# Landing_Gear_Layout_REV.net
KiCad netlist of a schematic drawn in EAGLE
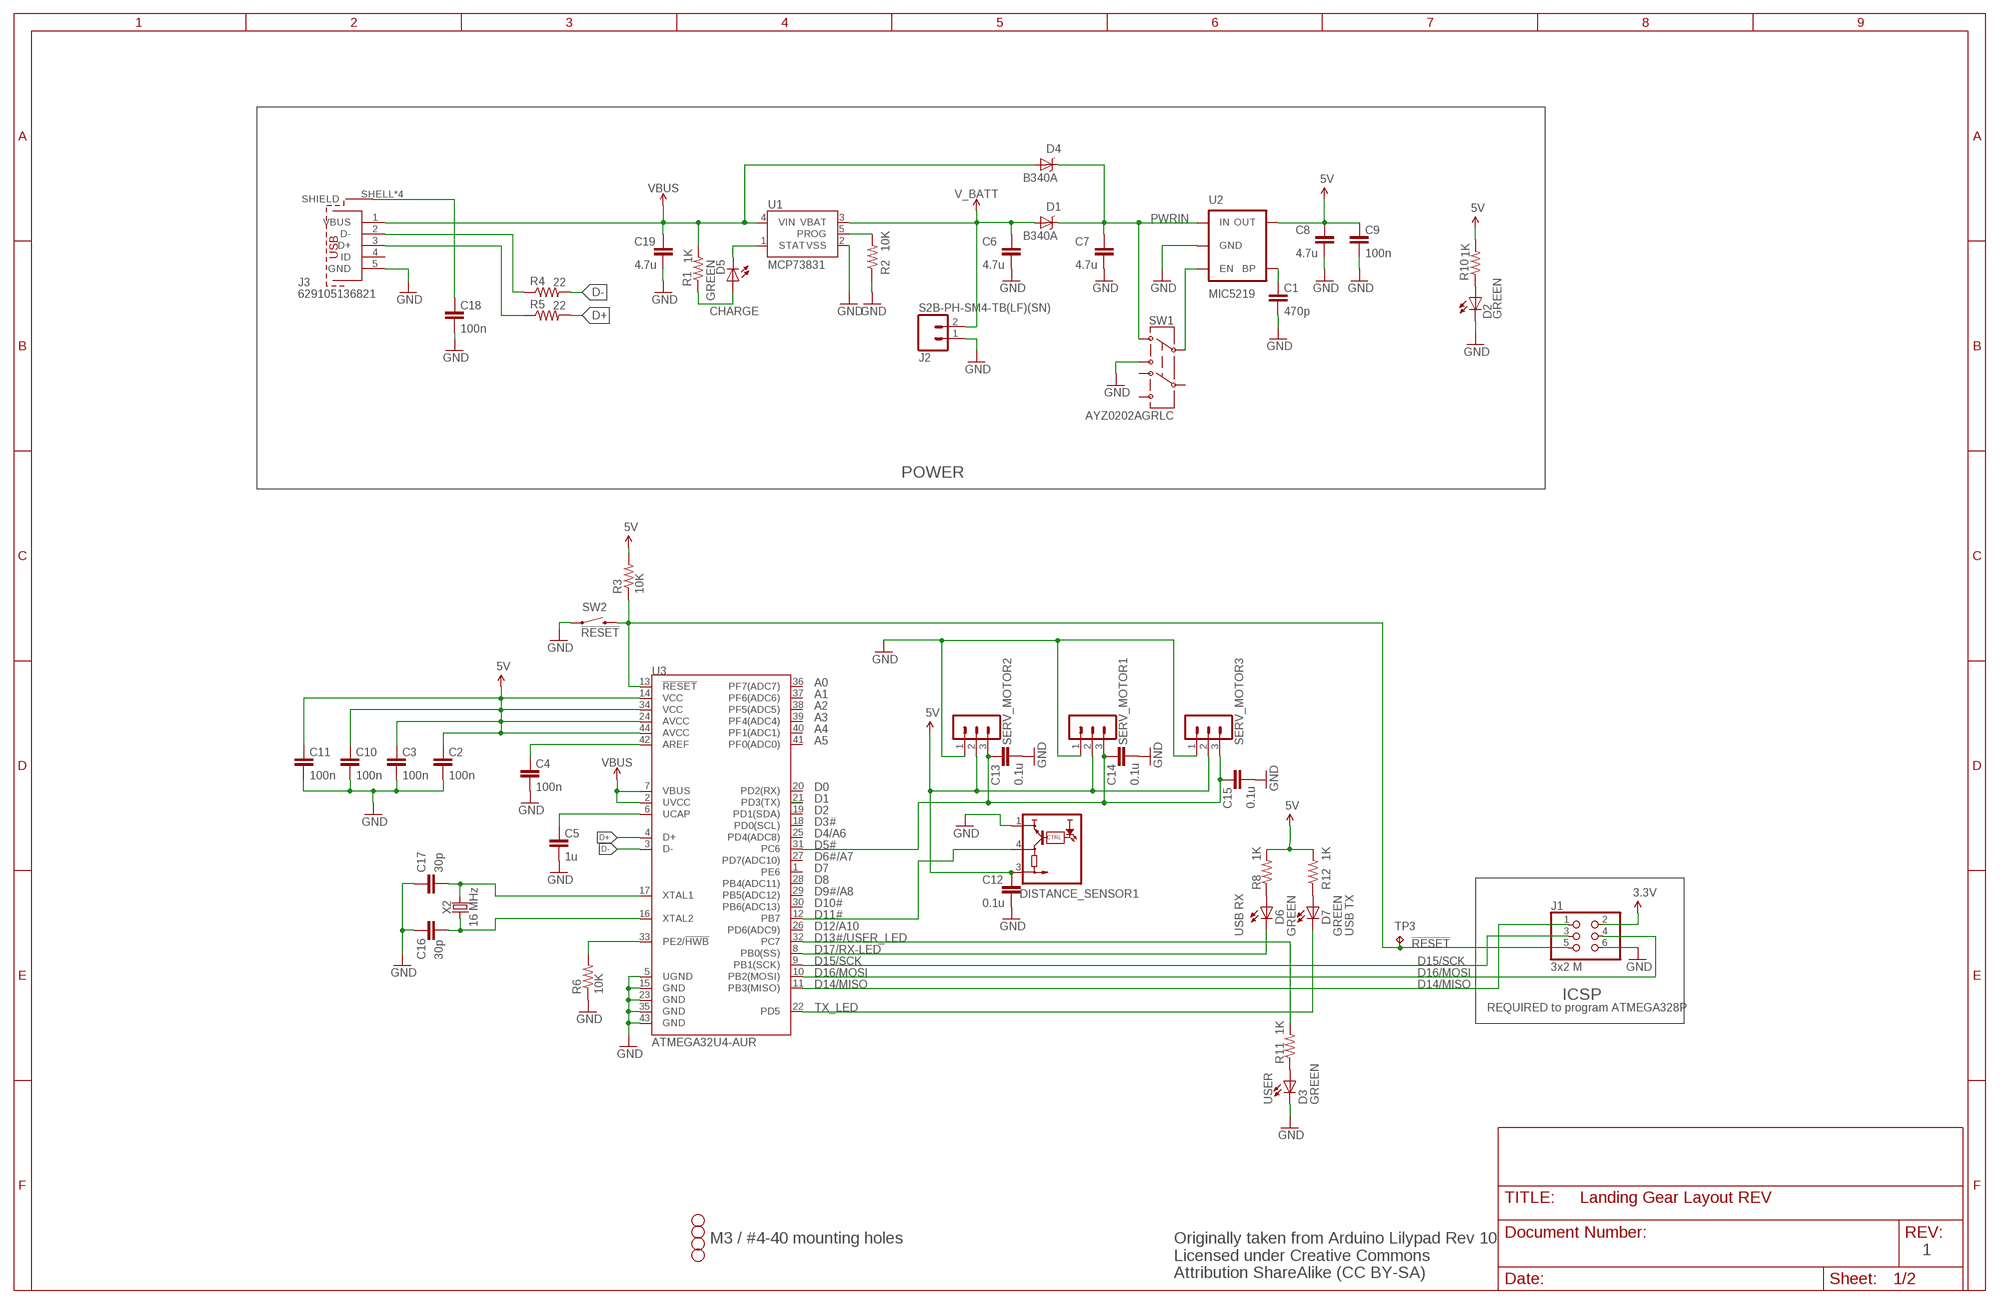
[diagram p0: schematic, sheet 1]

(export (version "E")
  (design (tool "Eeschema 10.0.6"))
  (components
    (comp (ref "C1")
      (value "470p")
      (footprint "eagle-import:C0805K")
      (fields (field (name "MFR") "Samsung") (field (name "MPN") "CL21B471KBANNNC"))
      (libsource (lib "eagle-import") (part "C-EUC0805K"))
    )
    (comp (ref "C2")
      (value "100n")
      (footprint "eagle-import:C0805K")
      (fields (field (name "MFR") "Samsung") (field (name "MPN") "CL21B104KBCNNNC"))
      (libsource (lib "eagle-import") (part "C-EUC0805K"))
    )
    (comp (ref "C3")
      (value "100n")
      (footprint "eagle-import:C0805K")
      (fields (field (name "MFR") "Samsung") (field (name "MPN") "CL21B104KBCNNNC"))
      (libsource (lib "eagle-import") (part "C-EUC0805K"))
    )
    (comp (ref "C4")
      (value "100n")
      (footprint "eagle-import:C0805K")
      (fields (field (name "MFR") "Samsung") (field (name "MPN") "CL21B104KBCNNNC"))
      (libsource (lib "eagle-import") (part "C-EUC0805K"))
    )
    (comp (ref "C5")
      (value "1u")
      (footprint "eagle-import:C0805K")
      (fields (field (name "MFR") "Samsung") (field (name "MPN") "CL21B105KOFNNNG"))
      (libsource (lib "eagle-import") (part "C-EUC0805K"))
    )
    (comp (ref "C6")
      (value "4.7u")
      (footprint "eagle-import:C0805K")
      (fields (field (name "MFR") "Samsung") (field (name "MPN") "CL21A475KOFNNNE"))
      (libsource (lib "eagle-import") (part "C-EUC0805K"))
    )
    (comp (ref "C7")
      (value "4.7u")
      (footprint "eagle-import:C0805K")
      (fields (field (name "MFR") "Samsung") (field (name "MPN") "CL21A475KOFNNNE"))
      (libsource (lib "eagle-import") (part "C-EUC0805K"))
    )
    (comp (ref "C8")
      (value "4.7u")
      (footprint "eagle-import:C0805K")
      (fields (field (name "MFR") "Samsung") (field (name "MPN") "CL21A475KOFNNNE"))
      (libsource (lib "eagle-import") (part "C-EUC0805K"))
    )
    (comp (ref "C9")
      (value "100n")
      (footprint "eagle-import:C0805K")
      (fields (field (name "MFR") "Samsung") (field (name "MPN") "CL21B104KBCNNNC"))
      (libsource (lib "eagle-import") (part "C-EUC0805K"))
    )
    (comp (ref "C10")
      (value "100n")
      (footprint "eagle-import:C0805K")
      (fields (field (name "MFR") "Samsung") (field (name "MPN") "CL21B104KBCNNNC"))
      (libsource (lib "eagle-import") (part "C-EUC0805K"))
    )
    (comp (ref "C11")
      (value "100n")
      (footprint "eagle-import:C0805K")
      (fields (field (name "MFR") "Samsung") (field (name "MPN") "CL21B104KBCNNNC"))
      (libsource (lib "eagle-import") (part "C-EUC0805K"))
    )
    (comp (ref "C12")
      (value "0.1u")
      (footprint "eagle-import:C0805K")
      (fields (field (name "MFR") "Samsung") (field (name "MPN") "CL21B105KOFNNNG"))
      (libsource (lib "eagle-import") (part "C-EUC0805K"))
    )
    (comp (ref "C13")
      (value "0.1u")
      (footprint "eagle-import:C0805K")
      (fields (field (name "MFR") "Samsung") (field (name "MPN") "CL21B105KOFNNNG"))
      (libsource (lib "eagle-import") (part "C-EUC0805K"))
    )
    (comp (ref "C14")
      (value "0.1u")
      (footprint "eagle-import:C0805K")
      (fields (field (name "MFR") "Samsung") (field (name "MPN") "CL21B105KOFNNNG"))
      (libsource (lib "eagle-import") (part "C-EUC0805K"))
    )
    (comp (ref "C15")
      (value "0.1u")
      (footprint "eagle-import:C0805K")
      (fields (field (name "MFR") "Samsung") (field (name "MPN") "CL21B105KOFNNNG"))
      (libsource (lib "eagle-import") (part "C-EUC0805K"))
    )
    (comp (ref "C16")
      (value "30p")
      (footprint "eagle-import:C0805K")
      (fields (field (name "MFR") "Samsung") (field (name "MPN") "CL21C300JBANNNC"))
      (libsource (lib "eagle-import") (part "C-EUC0805K"))
    )
    (comp (ref "C17")
      (value "30p")
      (footprint "eagle-import:C0805K")
      (fields (field (name "MFR") "Samsung") (field (name "MPN") "CL21C180JBANNNC"))
      (libsource (lib "eagle-import") (part "C-EUC0805K"))
    )
    (comp (ref "C18")
      (value "100n")
      (footprint "eagle-import:C0805K")
      (fields (field (name "MFR") "Samsung") (field (name "MPN") "CL21B104KBCNNNC"))
      (libsource (lib "eagle-import") (part "C-EUC0805K"))
    )
    (comp (ref "C19")
      (value "4.7u")
      (footprint "eagle-import:C0805K")
      (fields (field (name "MFR") "Samsung") (field (name "MPN") "CL21A475KOFNNNE"))
      (libsource (lib "eagle-import") (part "C-EUC0805K"))
    )
    (comp (ref "D1")
      (value "B340A")
      (footprint "eagle-import:SMA-DIODE")
      (fields (field (name "MFR") "Diodes Inc") (field (name "MPN") "B340AE-13"))
      (libsource (lib "eagle-import") (part "DIODE-SCHOTTKY_"))
    )
    (comp (ref "D2")
      (value "GREEN")
      (footprint "eagle-import:CHIP-LED0805")
      (fields (field (name "MFR") "Würth Elektronik") (field (name "MPN") "150080GS75000"))
      (libsource (lib "eagle-import") (part "LEDCHIP-LED0805"))
    )
    (comp (ref "D3")
      (value "GREEN")
      (footprint "eagle-import:CHIP-LED0805")
      (fields (field (name "MFR") "Würth Elektronik") (field (name "MPN") "150080GS75000"))
      (libsource (lib "eagle-import") (part "LEDCHIP-LED0805"))
    )
    (comp (ref "D4")
      (value "B340A")
      (footprint "eagle-import:SMA-DIODE")
      (fields (field (name "MFR") "Diodes Inc") (field (name "MPN") "B340AE-13"))
      (libsource (lib "eagle-import") (part "DIODE-SCHOTTKY_"))
    )
    (comp (ref "D5")
      (value "GREEN")
      (footprint "eagle-import:CHIP-LED0805")
      (fields (field (name "MFR") "Würth Elektronik") (field (name "MPN") "150080GS75000"))
      (libsource (lib "eagle-import") (part "LEDCHIP-LED0805"))
    )
    (comp (ref "D6")
      (value "GREEN")
      (footprint "eagle-import:CHIP-LED0805")
      (fields (field (name "MFR") "Würth Elektronik") (field (name "MPN") "150080GS75000"))
      (libsource (lib "eagle-import") (part "LEDCHIP-LED0805"))
    )
    (comp (ref "D7")
      (value "GREEN")
      (footprint "eagle-import:CHIP-LED0805")
      (fields (field (name "MFR") "Würth Elektronik") (field (name "MPN") "150080GS75000"))
      (libsource (lib "eagle-import") (part "LEDCHIP-LED0805"))
    )
    (comp (ref "DISTANCE_SENSOR1")
      (value "TSSP6P38")
      (footprint "eagle-import:TSSP6P38")
      (libsource (lib "eagle-import") (part "TSSP6P38"))
    )
    (comp (ref "H1")
      (value "STAND-OFF")
      (footprint "eagle-import:STAND-OFF")
      (libsource (lib "eagle-import") (part "STAND-OFF"))
    )
    (comp (ref "H2")
      (value "STAND-OFF")
      (footprint "eagle-import:STAND-OFF")
      (libsource (lib "eagle-import") (part "STAND-OFF"))
    )
    (comp (ref "H3")
      (value "STAND-OFF")
      (footprint "eagle-import:STAND-OFF")
      (libsource (lib "eagle-import") (part "STAND-OFF"))
    )
    (comp (ref "H4")
      (value "STAND-OFF")
      (footprint "eagle-import:STAND-OFF")
      (libsource (lib "eagle-import") (part "STAND-OFF"))
    )
    (comp (ref "J1")
      (value "3x2 M")
      (footprint "eagle-import:2X03")
      (fields (field (name "MFR") "Harwin") (field (name "MPN") "M20-9980345"))
      (libsource (lib "eagle-import") (part "PINHD-2X3"))
    )
    (comp (ref "J2")
      (value "S2B-PH-SM4-TB(LF)(SN)")
      (footprint "eagle-import:JST-2-SMD")
      (fields (field (name "MFR") "JST"))
      (libsource (lib "eagle-import") (part "M02-JST-2MM-SMT"))
    )
    (comp (ref "J3")
      (value "629105136821")
      (footprint "eagle-import:629105136821")
      (fields (field (name "MFR") "Wurth"))
      (libsource (lib "eagle-import") (part "629105136821"))
    )
    (comp (ref "R1")
      (value "1K")
      (footprint "eagle-import:R0805")
      (fields (field (name "MFR") "Yageo") (field (name "MPN") "RC0805FR-071KL"))
      (libsource (lib "eagle-import") (part "R-US_R0805"))
    )
    (comp (ref "R2")
      (value "10K")
      (footprint "eagle-import:R0805")
      (fields (field (name "MFR") "Yageo") (field (name "MPN") "RC0805FR-0710KL"))
      (libsource (lib "eagle-import") (part "R-US_R0805"))
    )
    (comp (ref "R3")
      (value "10K")
      (footprint "eagle-import:R0805")
      (fields (field (name "MFR") "Yageo") (field (name "MPN") "RC0805FR-0710KL"))
      (libsource (lib "eagle-import") (part "R-US_R0805"))
    )
    (comp (ref "R4")
      (value "22")
      (footprint "eagle-import:R0805")
      (fields (field (name "MFR") "Yageo") (field (name "MPN") "RC0805FR-0722RL"))
      (libsource (lib "eagle-import") (part "R-US_R0805"))
    )
    (comp (ref "R5")
      (value "22")
      (footprint "eagle-import:R0805")
      (fields (field (name "MFR") "Yageo") (field (name "MPN") "RC0805FR-0722RL"))
      (libsource (lib "eagle-import") (part "R-US_R0805"))
    )
    (comp (ref "R6")
      (value "10K")
      (footprint "eagle-import:R0805")
      (fields (field (name "MFR") "Yageo") (field (name "MPN") "RC0805FR-0710KL"))
      (libsource (lib "eagle-import") (part "R-US_R0805"))
    )
    (comp (ref "R8")
      (value "1K")
      (footprint "eagle-import:R0805")
      (fields (field (name "MFR") "Yageo") (field (name "MPN") "RC0805FR-071KL"))
      (libsource (lib "eagle-import") (part "R-US_R0805"))
    )
    (comp (ref "R10")
      (value "1K")
      (footprint "eagle-import:R0805")
      (fields (field (name "MFR") "Yageo") (field (name "MPN") "RC0805FR-071KL"))
      (libsource (lib "eagle-import") (part "R-US_R0805"))
    )
    (comp (ref "R11")
      (value "1K")
      (footprint "eagle-import:R0805")
      (fields (field (name "MFR") "Yageo") (field (name "MPN") "RC0805FR-071KL"))
      (libsource (lib "eagle-import") (part "R-US_R0805"))
    )
    (comp (ref "R12")
      (value "1K")
      (footprint "eagle-import:R0805")
      (fields (field (name "MFR") "Yageo") (field (name "MPN") "RC0805FR-071KL"))
      (libsource (lib "eagle-import") (part "R-US_R0805"))
    )
    (comp (ref "SERV_MOTOR1")
      (value "MA03-1")
      (footprint "eagle-import:MA03-1")
      (libsource (lib "eagle-import") (part "MA03-1"))
    )
    (comp (ref "SERV_MOTOR2")
      (value "MA03-1")
      (footprint "eagle-import:MA03-1")
      (libsource (lib "eagle-import") (part "MA03-1"))
    )
    (comp (ref "SERV_MOTOR3")
      (value "MA03-1")
      (footprint "eagle-import:MA03-1")
      (libsource (lib "eagle-import") (part "MA03-1"))
    )
    (comp (ref "SW1")
      (value "AYZ0202AGRLC")
      (footprint "eagle-import:AYZ0202")
      (fields (field (name "MFR") "C&K"))
      (libsource (lib "eagle-import") (part "SWITCH-DPDTSMD"))
    )
    (comp (ref "SW2")
      (value "!RESET")
      (footprint "eagle-import:TACTILE_SWITCH_SMD")
      (fields (field (name "MFR") "C&K") (field (name "MPN") "RS-187R05A2-DS MT RT"))
      (libsource (lib "eagle-import") (part "SWITCH-MOMENTARY-2SMD"))
    )
    (comp (ref "TP3")
      (value "TPPAD1-13")
      (footprint "eagle-import:P1-13")
      (libsource (lib "eagle-import") (part "TPPAD1-13"))
    )
    (comp (ref "U1")
      (value "MCP73831")
      (footprint "eagle-import:SOT23-5")
      (fields (field (name "MFR") "Microchip") (field (name "MPN") "MCP73831T-2ACI/OT"))
      (libsource (lib "eagle-import") (part "MCP73831"))
    )
    (comp (ref "U2")
      (value "MIC5219")
      (footprint "eagle-import:SOT23-5")
      (fields (field (name "MFR") "Microchip") (field (name "MPN") "MIC5219-3.3YM5-TR"))
      (libsource (lib "eagle-import") (part "V_REG_MIC5219SMD"))
    )
    (comp (ref "U3")
      (value "ATMEGA32U4-AUR")
      (footprint "eagle-import:TQFP44")
      (fields (field (name "MFR") "Microchip") (field (name "PROD_ID") "IC-10828"))
      (libsource (lib "eagle-import") (part "ATMEGA32U4TQFP-44"))
    )
    (comp (ref "X2")
      (value "16 MHz")
      (footprint "eagle-import:HC49UP")
      (fields (field (name "MFR") "ECS") (field (name "MPN") "ECS-160-18-5PX-TR"))
      (libsource (lib "eagle-import") (part "CRYSTALSMD-HC49UP"))
    )
  )
  (nets
    (net (code "1") (name "3.3V") (class "Default")
      (node (ref "C10") (pin "1") (pinfunction "1_1") (pintype "passive"))
      (node (ref "C11") (pin "1") (pinfunction "1_1") (pintype "passive"))
      (node (ref "C12") (pin "1") (pinfunction "1_1") (pintype "passive"))
      (node (ref "C2") (pin "1") (pinfunction "1_1") (pintype "passive"))
      (node (ref "C3") (pin "1") (pinfunction "1_1") (pintype "passive"))
      (node (ref "C8") (pin "1") (pinfunction "1_1") (pintype "passive"))
      (node (ref "C9") (pin "1") (pinfunction "1_1") (pintype "passive"))
      (node (ref "DISTANCE_SENSOR1") (pin "3") (pinfunction "VS_3") (pintype "power_in"))
      (node (ref "J1") (pin "2") (pinfunction "2_2") (pintype "passive"))
      (node (ref "R10") (pin "2") (pinfunction "2_2") (pintype "passive"))
      (node (ref "R12") (pin "2") (pinfunction "2_2") (pintype "passive"))
      (node (ref "R3") (pin "2") (pinfunction "2_2") (pintype "passive"))
      (node (ref "R8") (pin "2") (pinfunction "2_2") (pintype "passive"))
      (node (ref "SERV_MOTOR1") (pin "2") (pinfunction "2_2") (pintype "passive"))
      (node (ref "SERV_MOTOR2") (pin "2") (pinfunction "2_2") (pintype "passive"))
      (node (ref "SERV_MOTOR3") (pin "2") (pinfunction "2_2") (pintype "passive"))
      (node (ref "U2") (pin "5") (pinfunction "OUT_5") (pintype "passive"))
      (node (ref "U3") (pin "14") (pinfunction "VCC_14") (pintype "bidirectional"))
      (node (ref "U3") (pin "24") (pinfunction "AVCC_24") (pintype "bidirectional"))
      (node (ref "U3") (pin "34") (pinfunction "VCC_34") (pintype "bidirectional"))
      (node (ref "U3") (pin "44") (pinfunction "AVCC_44") (pintype "bidirectional"))
    )
    (net (code "2") (name "D+") (class "Default")
      (node (ref "R5") (pin "2") (pinfunction "2_2") (pintype "passive"))
      (node (ref "U3") (pin "4") (pinfunction "D+_4") (pintype "bidirectional"))
    )
    (net (code "3") (name "D-") (class "Default")
      (node (ref "R4") (pin "2") (pinfunction "2_2") (pintype "passive"))
      (node (ref "U3") (pin "3") (pinfunction "D-_3") (pintype "bidirectional"))
    )
    (net (code "4") (name "D13#{slash}USER_LED") (class "Default")
      (node (ref "R11") (pin "2") (pinfunction "2_2") (pintype "passive"))
      (node (ref "U3") (pin "32") (pinfunction "PC7_32") (pintype "bidirectional"))
    )
    (net (code "5") (name "D14{slash}MISO") (class "Default")
      (node (ref "J1") (pin "1") (pinfunction "1_1") (pintype "passive"))
      (node (ref "U3") (pin "11") (pinfunction "PB3(MISO)_11") (pintype "bidirectional"))
    )
    (net (code "6") (name "D15{slash}SCK") (class "Default")
      (node (ref "J1") (pin "3") (pinfunction "3_3") (pintype "passive"))
      (node (ref "U3") (pin "9") (pinfunction "PB1(SCK)_9") (pintype "bidirectional"))
    )
    (net (code "7") (name "D16{slash}MOSI") (class "Default")
      (node (ref "J1") (pin "4") (pinfunction "4_4") (pintype "passive"))
      (node (ref "U3") (pin "10") (pinfunction "PB2(MOSI)_10") (pintype "bidirectional"))
    )
    (net (code "8") (name "D17{slash}RX-LED") (class "Default")
      (node (ref "D6") (pin "C") (pinfunction "C_C") (pintype "passive"))
      (node (ref "U3") (pin "8") (pinfunction "PB0(SS)_8") (pintype "bidirectional"))
    )
    (net (code "9") (name "GND") (class "Default")
      (node (ref "C1") (pin "2") (pinfunction "2_2") (pintype "passive"))
      (node (ref "C10") (pin "2") (pinfunction "2_2") (pintype "passive"))
      (node (ref "C11") (pin "2") (pinfunction "2_2") (pintype "passive"))
      (node (ref "C12") (pin "2") (pinfunction "2_2") (pintype "passive"))
      (node (ref "C13") (pin "2") (pinfunction "2_2") (pintype "passive"))
      (node (ref "C14") (pin "2") (pinfunction "2_2") (pintype "passive"))
      (node (ref "C15") (pin "2") (pinfunction "2_2") (pintype "passive"))
      (node (ref "C16") (pin "2") (pinfunction "2_2") (pintype "passive"))
      (node (ref "C17") (pin "2") (pinfunction "2_2") (pintype "passive"))
      (node (ref "C18") (pin "2") (pinfunction "2_2") (pintype "passive"))
      (node (ref "C19") (pin "2") (pinfunction "2_2") (pintype "passive"))
      (node (ref "C2") (pin "2") (pinfunction "2_2") (pintype "passive"))
      (node (ref "C3") (pin "2") (pinfunction "2_2") (pintype "passive"))
      (node (ref "C4") (pin "2") (pinfunction "2_2") (pintype "passive"))
      (node (ref "C5") (pin "2") (pinfunction "2_2") (pintype "passive"))
      (node (ref "C6") (pin "2") (pinfunction "2_2") (pintype "passive"))
      (node (ref "C7") (pin "2") (pinfunction "2_2") (pintype "passive"))
      (node (ref "C8") (pin "2") (pinfunction "2_2") (pintype "passive"))
      (node (ref "C9") (pin "2") (pinfunction "2_2") (pintype "passive"))
      (node (ref "D2") (pin "C") (pinfunction "C_C") (pintype "passive"))
      (node (ref "D3") (pin "C") (pinfunction "C_C") (pintype "passive"))
      (node (ref "DISTANCE_SENSOR1") (pin "1") (pinfunction "GND_1") (pintype "power_in"))
      (node (ref "J1") (pin "6") (pinfunction "6_6") (pintype "passive"))
      (node (ref "J2") (pin "1") (pinfunction "2_1") (pintype "passive"))
      (node (ref "J3") (pin "5") (pinfunction "GND_5") (pintype "passive"))
      (node (ref "R2") (pin "1") (pinfunction "1_1") (pintype "passive"))
      (node (ref "R6") (pin "1") (pinfunction "1_1") (pintype "passive"))
      (node (ref "SERV_MOTOR1") (pin "1") (pinfunction "1_1") (pintype "passive"))
      (node (ref "SERV_MOTOR2") (pin "1") (pinfunction "1_1") (pintype "passive"))
      (node (ref "SERV_MOTOR3") (pin "1") (pinfunction "1_1") (pintype "passive"))
      (node (ref "SW1") (pin "3") (pinfunction "3_3") (pintype "bidirectional"))
      (node (ref "SW2") (pin "1") (pinfunction "1_1") (pintype "passive"))
      (node (ref "U1") (pin "2") (pinfunction "VSS_2") (pintype "power_in"))
      (node (ref "U2") (pin "2") (pinfunction "GND_2") (pintype "input"))
      (node (ref "U3") (pin "15") (pinfunction "GND_15") (pintype "bidirectional"))
      (node (ref "U3") (pin "23") (pinfunction "GND_23") (pintype "bidirectional"))
      (node (ref "U3") (pin "35") (pinfunction "GND_35") (pintype "bidirectional"))
      (node (ref "U3") (pin "43") (pinfunction "GND_43") (pintype "bidirectional"))
      (node (ref "U3") (pin "5") (pinfunction "UGND_5") (pintype "bidirectional"))
    )
    (net (code "10") (name "Net-(C18-Pad1)") (class "Default")
      (node (ref "C18") (pin "1") (pinfunction "1_1") (pintype "passive"))
      (node (ref "J3") (pin "SHELL") (pinfunction "SHIELD_SHELL") (pintype "passive"))
      (node (ref "J3") (pin "SHELL1") (pinfunction "SHIELD_SHELL1") (pintype "passive"))
      (node (ref "J3") (pin "SHELL2") (pinfunction "SHIELD_SHELL2") (pintype "passive"))
      (node (ref "J3") (pin "SHELL3") (pinfunction "SHIELD_SHELL3") (pintype "passive"))
    )
    (net (code "11") (name "Net-(D2-PadA)") (class "Default")
      (node (ref "D2") (pin "A") (pinfunction "A_A") (pintype "passive"))
      (node (ref "R10") (pin "1") (pinfunction "1_1") (pintype "passive"))
    )
    (net (code "12") (name "Net-(D3-PadA)") (class "Default")
      (node (ref "D3") (pin "A") (pinfunction "A_A") (pintype "passive"))
      (node (ref "R11") (pin "1") (pinfunction "1_1") (pintype "passive"))
    )
    (net (code "13") (name "Net-(D5-PadA)") (class "Default")
      (node (ref "D5") (pin "A") (pinfunction "A_A") (pintype "passive"))
      (node (ref "R1") (pin "1") (pinfunction "1_1") (pintype "passive"))
    )
    (net (code "14") (name "Net-(D6-PadA)") (class "Default")
      (node (ref "D6") (pin "A") (pinfunction "A_A") (pintype "passive"))
      (node (ref "R8") (pin "1") (pinfunction "1_1") (pintype "passive"))
    )
    (net (code "15") (name "Net-(D7-PadA)") (class "Default")
      (node (ref "D7") (pin "A") (pinfunction "A_A") (pintype "passive"))
      (node (ref "R12") (pin "1") (pinfunction "1_1") (pintype "passive"))
    )
    (net (code "16") (name "Net-(DISTANCE_SENSOR1-OUT)") (class "Default")
      (node (ref "DISTANCE_SENSOR1") (pin "4") (pinfunction "OUT_4") (pintype "output"))
      (node (ref "U3") (pin "12") (pinfunction "PB7_12") (pintype "bidirectional"))
    )
    (net (code "17") (name "Net-(J3-D+)") (class "Default")
      (node (ref "J3") (pin "3") (pinfunction "D+_3") (pintype "passive"))
      (node (ref "R5") (pin "1") (pinfunction "1_1") (pintype "passive"))
    )
    (net (code "18") (name "Net-(J3-D-)") (class "Default")
      (node (ref "J3") (pin "2") (pinfunction "D-_2") (pintype "passive"))
      (node (ref "R4") (pin "1") (pinfunction "1_1") (pintype "passive"))
    )
    (net (code "19") (name "Net-(U1-PROG)") (class "Default")
      (node (ref "R2") (pin "2") (pinfunction "2_2") (pintype "passive"))
      (node (ref "U1") (pin "5") (pinfunction "PROG_5") (pintype "input"))
    )
    (net (code "20") (name "Net-(U1-STAT)") (class "Default")
      (node (ref "D5") (pin "C") (pinfunction "C_C") (pintype "passive"))
      (node (ref "U1") (pin "1") (pinfunction "STAT_1") (pintype "output"))
    )
    (net (code "21") (name "Net-(U2-BP)") (class "Default")
      (node (ref "C1") (pin "1") (pinfunction "1_1") (pintype "passive"))
      (node (ref "U2") (pin "4") (pinfunction "BP_4") (pintype "input"))
    )
    (net (code "22") (name "Net-(U2-EN)") (class "Default")
      (node (ref "SW1") (pin "2") (pinfunction "2_2") (pintype "bidirectional"))
      (node (ref "U2") (pin "3") (pinfunction "EN_3") (pintype "input"))
    )
    (net (code "23") (name "Net-(U3-AREF)") (class "Default")
      (node (ref "C4") (pin "1") (pinfunction "1_1") (pintype "passive"))
      (node (ref "U3") (pin "42") (pinfunction "AREF_42") (pintype "bidirectional"))
    )
    (net (code "24") (name "Net-(U3-PC6)") (class "Default")
      (node (ref "C13") (pin "1") (pinfunction "1_1") (pintype "passive"))
      (node (ref "C14") (pin "1") (pinfunction "1_1") (pintype "passive"))
      (node (ref "C15") (pin "1") (pinfunction "1_1") (pintype "passive"))
      (node (ref "SERV_MOTOR1") (pin "3") (pinfunction "3_3") (pintype "passive"))
      (node (ref "SERV_MOTOR2") (pin "3") (pinfunction "3_3") (pintype "passive"))
      (node (ref "SERV_MOTOR3") (pin "3") (pinfunction "3_3") (pintype "passive"))
      (node (ref "U3") (pin "31") (pinfunction "PC6_31") (pintype "bidirectional"))
    )
    (net (code "25") (name "Net-(U3-PE2{slash}~{HWB})") (class "Default")
      (node (ref "R6") (pin "2") (pinfunction "2_2") (pintype "passive"))
      (node (ref "U3") (pin "33") (pinfunction "PE2/~{HWB}_33") (pintype "bidirectional"))
    )
    (net (code "26") (name "Net-(U3-UCAP)") (class "Default")
      (node (ref "C5") (pin "1") (pinfunction "1_1") (pintype "passive"))
      (node (ref "U3") (pin "6") (pinfunction "UCAP_6") (pintype "bidirectional"))
    )
    (net (code "27") (name "Net-(U3-XTAL1)") (class "Default")
      (node (ref "C17") (pin "1") (pinfunction "1_1") (pintype "passive"))
      (node (ref "U3") (pin "17") (pinfunction "XTAL1_17") (pintype "bidirectional"))
      (node (ref "X2") (pin "2") (pinfunction "2_2") (pintype "passive"))
    )
    (net (code "28") (name "Net-(U3-XTAL2)") (class "Default")
      (node (ref "C16") (pin "1") (pinfunction "1_1") (pintype "passive"))
      (node (ref "U3") (pin "16") (pinfunction "XTAL2_16") (pintype "bidirectional"))
      (node (ref "X2") (pin "1") (pinfunction "1_1") (pintype "passive"))
    )
    (net (code "29") (name "PWRIN") (class "Default")
      (node (ref "C7") (pin "1") (pinfunction "1_1") (pintype "passive"))
      (node (ref "D1") (pin "C") (pinfunction "C_C") (pintype "passive"))
      (node (ref "D4") (pin "C") (pinfunction "C_C") (pintype "passive"))
      (node (ref "SW1") (pin "1") (pinfunction "1_1") (pintype "bidirectional"))
      (node (ref "U2") (pin "1") (pinfunction "IN_1") (pintype "input"))
    )
    (net (code "30") (name "TX_LED") (class "Default")
      (node (ref "D7") (pin "C") (pinfunction "C_C") (pintype "passive"))
      (node (ref "U3") (pin "22") (pinfunction "PD5_22") (pintype "bidirectional"))
    )
    (net (code "31") (name "VBUS") (class "Default")
      (node (ref "C19") (pin "1") (pinfunction "1_1") (pintype "passive"))
      (node (ref "D4") (pin "A") (pinfunction "A_A") (pintype "passive"))
      (node (ref "J3") (pin "1") (pinfunction "VBUS_1") (pintype "passive"))
      (node (ref "R1") (pin "2") (pinfunction "2_2") (pintype "passive"))
      (node (ref "U1") (pin "4") (pinfunction "VIN_4") (pintype "power_in"))
      (node (ref "U3") (pin "2") (pinfunction "UVCC_2") (pintype "bidirectional"))
      (node (ref "U3") (pin "7") (pinfunction "VBUS_7") (pintype "bidirectional"))
    )
    (net (code "32") (name "V_BATT") (class "Default")
      (node (ref "C6") (pin "1") (pinfunction "1_1") (pintype "passive"))
      (node (ref "D1") (pin "A") (pinfunction "A_A") (pintype "passive"))
      (node (ref "J2") (pin "2") (pinfunction "1_2") (pintype "passive"))
      (node (ref "U1") (pin "3") (pinfunction "VBAT_3") (pintype "power_in"))
    )
    (net (code "33") (name "unconnected-(J3-ID-Pad4)") (class "Default")
      (node (ref "J3") (pin "4") (pinfunction "ID_4") (pintype "passive"))
    )
    (net (code "34") (name "unconnected-(SW1-Pad4)") (class "Default")
      (node (ref "SW1") (pin "4") (pinfunction "4_4") (pintype "bidirectional"))
    )
    (net (code "35") (name "unconnected-(SW1-Pad5)") (class "Default")
      (node (ref "SW1") (pin "5") (pinfunction "5_5") (pintype "bidirectional"))
    )
    (net (code "36") (name "unconnected-(SW1-Pad6)") (class "Default")
      (node (ref "SW1") (pin "6") (pinfunction "6_6") (pintype "bidirectional"))
    )
    (net (code "37") (name "unconnected-(U3-PB4(ADC11)-Pad28)") (class "Default")
      (node (ref "U3") (pin "28") (pinfunction "PB4(ADC11)_28") (pintype "bidirectional"))
    )
    (net (code "38") (name "unconnected-(U3-PB5(ADC12)-Pad29)") (class "Default")
      (node (ref "U3") (pin "29") (pinfunction "PB5(ADC12)_29") (pintype "bidirectional"))
    )
    (net (code "39") (name "unconnected-(U3-PB6(ADC13)-Pad30)") (class "Default")
      (node (ref "U3") (pin "30") (pinfunction "PB6(ADC13)_30") (pintype "bidirectional"))
    )
    (net (code "40") (name "unconnected-(U3-PD0(SCL)-Pad18)") (class "Default")
      (node (ref "U3") (pin "18") (pinfunction "PD0(SCL)_18") (pintype "bidirectional"))
    )
    (net (code "41") (name "unconnected-(U3-PD1(SDA)-Pad19)") (class "Default")
      (node (ref "U3") (pin "19") (pinfunction "PD1(SDA)_19") (pintype "bidirectional"))
    )
    (net (code "42") (name "unconnected-(U3-PD2(RX)-Pad20)") (class "Default")
      (node (ref "U3") (pin "20") (pinfunction "PD2(RX)_20") (pintype "bidirectional"))
    )
    (net (code "43") (name "unconnected-(U3-PD3(TX)-Pad21)") (class "Default")
      (node (ref "U3") (pin "21") (pinfunction "PD3(TX)_21") (pintype "bidirectional"))
    )
    (net (code "44") (name "unconnected-(U3-PD4(ADC8)-Pad25)") (class "Default")
      (node (ref "U3") (pin "25") (pinfunction "PD4(ADC8)_25") (pintype "bidirectional"))
    )
    (net (code "45") (name "unconnected-(U3-PD6(ADC9)-Pad26)") (class "Default")
      (node (ref "U3") (pin "26") (pinfunction "PD6(ADC9)_26") (pintype "bidirectional"))
    )
    (net (code "46") (name "unconnected-(U3-PD7(ADC10)-Pad27)") (class "Default")
      (node (ref "U3") (pin "27") (pinfunction "PD7(ADC10)_27") (pintype "bidirectional"))
    )
    (net (code "47") (name "unconnected-(U3-PE6-Pad1)") (class "Default")
      (node (ref "U3") (pin "1") (pinfunction "PE6_1") (pintype "bidirectional"))
    )
    (net (code "48") (name "unconnected-(U3-PF0(ADC0)-Pad41)") (class "Default")
      (node (ref "U3") (pin "41") (pinfunction "PF0(ADC0)_41") (pintype "bidirectional"))
    )
    (net (code "49") (name "unconnected-(U3-PF1(ADC1)-Pad40)") (class "Default")
      (node (ref "U3") (pin "40") (pinfunction "PF1(ADC1)_40") (pintype "bidirectional"))
    )
    (net (code "50") (name "unconnected-(U3-PF4(ADC4)-Pad39)") (class "Default")
      (node (ref "U3") (pin "39") (pinfunction "PF4(ADC4)_39") (pintype "bidirectional"))
    )
    (net (code "51") (name "unconnected-(U3-PF5(ADC5)-Pad38)") (class "Default")
      (node (ref "U3") (pin "38") (pinfunction "PF5(ADC5)_38") (pintype "bidirectional"))
    )
    (net (code "52") (name "unconnected-(U3-PF6(ADC6)-Pad37)") (class "Default")
      (node (ref "U3") (pin "37") (pinfunction "PF6(ADC6)_37") (pintype "bidirectional"))
    )
    (net (code "53") (name "unconnected-(U3-PF7(ADC7)-Pad36)") (class "Default")
      (node (ref "U3") (pin "36") (pinfunction "PF7(ADC7)_36") (pintype "bidirectional"))
    )
    (net (code "54") (name "~{RESET}") (class "Default")
      (node (ref "J1") (pin "5") (pinfunction "5_5") (pintype "passive"))
      (node (ref "R3") (pin "1") (pinfunction "1_1") (pintype "passive"))
      (node (ref "SW2") (pin "3") (pinfunction "2_3") (pintype "passive"))
      (node (ref "TP3") (pin "TP") (pinfunction "TP_TP") (pintype "input"))
      (node (ref "U3") (pin "13") (pinfunction "~{RESET}_13") (pintype "bidirectional"))
    )
  )
)
